# RaspPlaca.net
KiCad netlist of a schematic drawn in EAGLE
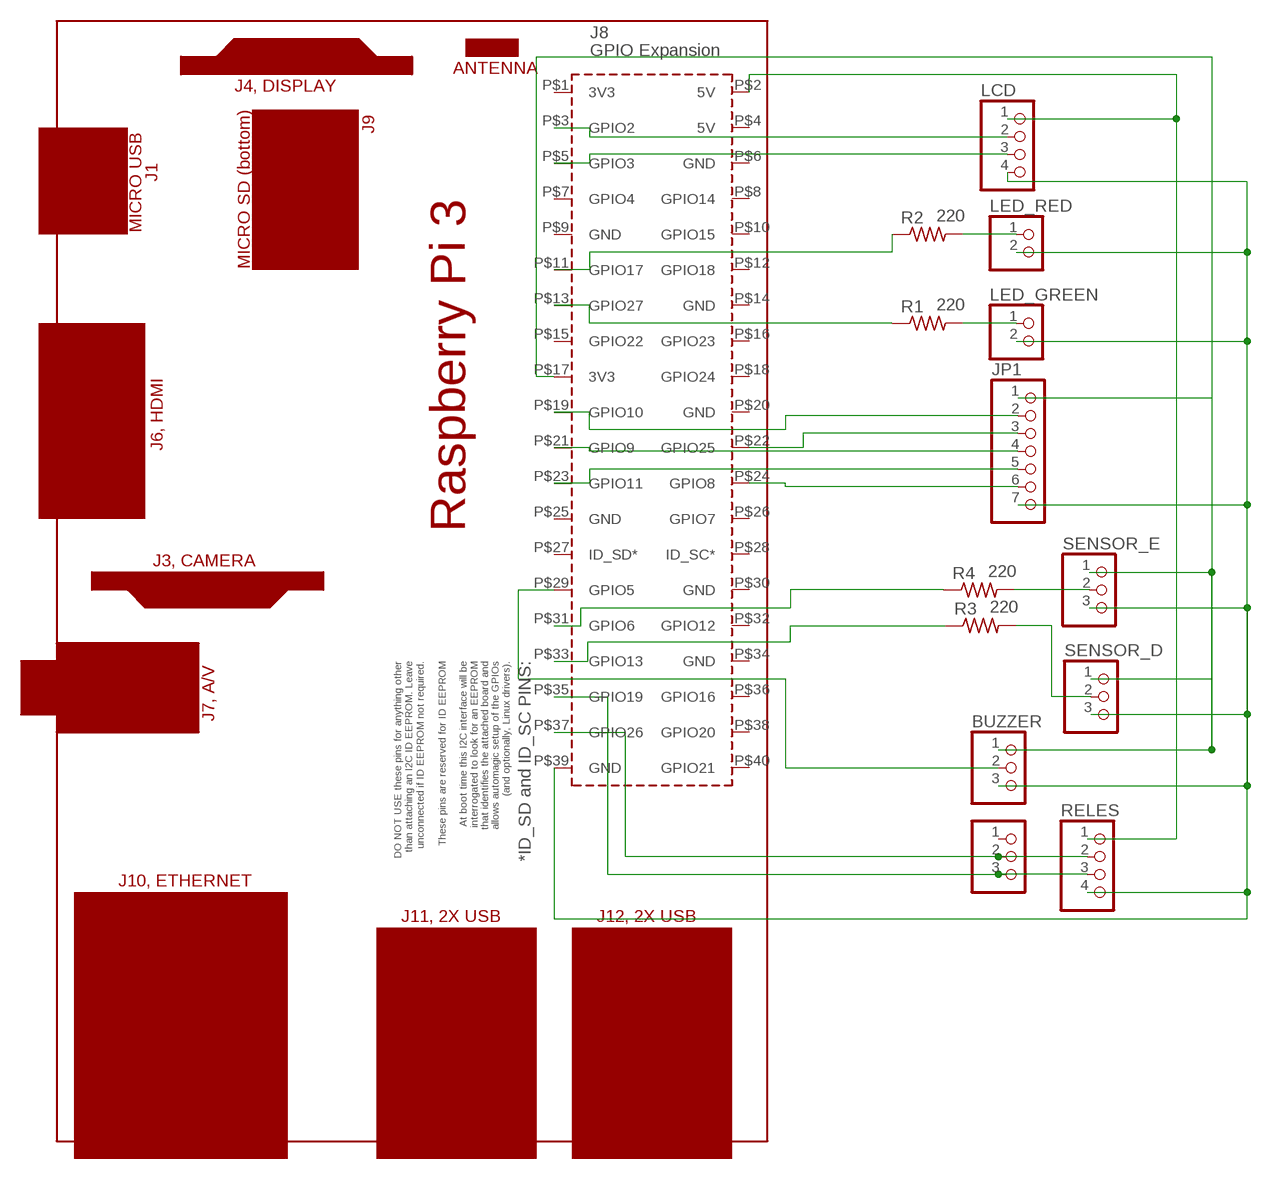
[diagram p0: schematic, sheet 1]

(export (version "E")
  (design (tool "Eeschema 10.0.6"))
  (components
    (comp (ref "BUZZER")
      (value "PINHD-1X3")
      (footprint "eagle-import:1X03")
      (libsource (lib "eagle-import") (part "PINHD-1X3"))
    )
    (comp (ref "JP1")
      (value "PINHD-1X7")
      (footprint "eagle-import:1X07")
      (libsource (lib "eagle-import") (part "PINHD-1X7"))
    )
    (comp (ref "LCD")
      (value "PINHD-1X4")
      (footprint "eagle-import:1X04")
      (libsource (lib "eagle-import") (part "PINHD-1X4"))
    )
    (comp (ref "LED_GREEN")
      (value "PINHD-1X2")
      (footprint "eagle-import:1X02")
      (libsource (lib "eagle-import") (part "PINHD-1X2"))
    )
    (comp (ref "LED_RED")
      (value "PINHD-1X2")
      (footprint "eagle-import:1X02")
      (libsource (lib "eagle-import") (part "PINHD-1X2"))
    )
    (comp (ref "PCB1")
      (value "RPI3RPI3")
      (footprint "eagle-import:RPI3")
      (libsource (lib "eagle-import") (part "RPI3RPI3"))
    )
    (comp (ref "R1")
      (value "220")
      (footprint "eagle-import:0207_10")
      (libsource (lib "eagle-import") (part "R-US_0207/10"))
    )
    (comp (ref "R2")
      (value "220")
      (footprint "eagle-import:0207_10")
      (libsource (lib "eagle-import") (part "R-US_0207/10"))
    )
    (comp (ref "R3")
      (value "220")
      (footprint "eagle-import:0207_10")
      (libsource (lib "eagle-import") (part "R-US_0207/10"))
    )
    (comp (ref "R4")
      (value "220")
      (footprint "eagle-import:0207_10")
      (libsource (lib "eagle-import") (part "R-US_0207/10"))
    )
    (comp (ref "RELES")
      (value "PINHD-1X4")
      (footprint "eagle-import:1X04")
      (libsource (lib "eagle-import") (part "PINHD-1X4"))
    )
    (comp (ref "SENSOR_D")
      (value "PINHD-1X3")
      (footprint "eagle-import:1X03")
      (libsource (lib "eagle-import") (part "PINHD-1X3"))
    )
    (comp (ref "SENSOR_E")
      (value "PINHD-1X3")
      (footprint "eagle-import:1X03")
      (libsource (lib "eagle-import") (part "PINHD-1X3"))
    )
    (comp (ref "UNIFICADOR_RELES")
      (value "PINHD-1X3")
      (footprint "eagle-import:1X03")
      (libsource (lib "eagle-import") (part "PINHD-1X3"))
    )
  )
  (nets
    (net (code "1") (name "Net-(BUZZER-Pad1)") (class "Default")
      (node (ref "BUZZER") (pin "1") (pinfunction "1_1") (pintype "passive"))
      (node (ref "JP1") (pin "1") (pinfunction "1_1") (pintype "passive"))
      (node (ref "PCB1") (pin "P$17") (pinfunction "3V3_P$17") (pintype "bidirectional"))
      (node (ref "SENSOR_D") (pin "1") (pinfunction "1_1") (pintype "passive"))
      (node (ref "SENSOR_E") (pin "1") (pinfunction "1_1") (pintype "passive"))
    )
    (net (code "2") (name "Net-(BUZZER-Pad3)") (class "Default")
      (node (ref "BUZZER") (pin "3") (pinfunction "3_3") (pintype "passive"))
      (node (ref "JP1") (pin "7") (pinfunction "7_7") (pintype "passive"))
      (node (ref "LCD") (pin "4") (pinfunction "4_4") (pintype "passive"))
      (node (ref "LED_GREEN") (pin "2") (pinfunction "2_2") (pintype "passive"))
      (node (ref "LED_RED") (pin "2") (pinfunction "2_2") (pintype "passive"))
      (node (ref "PCB1") (pin "P$39") (pinfunction "GND_P$39") (pintype "bidirectional"))
      (node (ref "RELES") (pin "4") (pinfunction "4_4") (pintype "passive"))
      (node (ref "SENSOR_D") (pin "3") (pinfunction "3_3") (pintype "passive"))
      (node (ref "SENSOR_E") (pin "3") (pinfunction "3_3") (pintype "passive"))
    )
    (net (code "3") (name "Net-(LCD-Pad1)") (class "Default")
      (node (ref "LCD") (pin "1") (pinfunction "1_1") (pintype "passive"))
      (node (ref "PCB1") (pin "P$2") (pinfunction "5V_P$2") (pintype "bidirectional"))
      (node (ref "RELES") (pin "1") (pinfunction "1_1") (pintype "passive"))
    )
    (net (code "4") (name "Net-(LED_GREEN-Pad1)") (class "Default")
      (node (ref "LED_GREEN") (pin "1") (pinfunction "1_1") (pintype "passive"))
      (node (ref "R1") (pin "2") (pinfunction "2_2") (pintype "passive"))
    )
    (net (code "5") (name "Net-(LED_RED-Pad1)") (class "Default")
      (node (ref "LED_RED") (pin "1") (pinfunction "1_1") (pintype "passive"))
      (node (ref "R2") (pin "2") (pinfunction "2_2") (pintype "passive"))
    )
    (net (code "6") (name "Net-(PCB1-GPIO2)") (class "Default")
      (node (ref "LCD") (pin "2") (pinfunction "2_2") (pintype "passive"))
      (node (ref "PCB1") (pin "P$3") (pinfunction "GPIO2_P$3") (pintype "bidirectional"))
    )
    (net (code "7") (name "Net-(PCB1-GPIO3)") (class "Default")
      (node (ref "LCD") (pin "3") (pinfunction "3_3") (pintype "passive"))
      (node (ref "PCB1") (pin "P$5") (pinfunction "GPIO3_P$5") (pintype "bidirectional"))
    )
    (net (code "8") (name "Net-(PCB1-GPIO5)") (class "Default")
      (node (ref "BUZZER") (pin "2") (pinfunction "2_2") (pintype "passive"))
      (node (ref "PCB1") (pin "P$29") (pinfunction "GPIO5_P$29") (pintype "bidirectional"))
    )
    (net (code "9") (name "Net-(PCB1-GPIO6)") (class "Default")
      (node (ref "PCB1") (pin "P$31") (pinfunction "GPIO6_P$31") (pintype "bidirectional"))
      (node (ref "R4") (pin "1") (pinfunction "1_1") (pintype "passive"))
    )
    (net (code "10") (name "Net-(PCB1-GPIO8)") (class "Default")
      (node (ref "JP1") (pin "6") (pinfunction "6_6") (pintype "passive"))
      (node (ref "PCB1") (pin "P$24") (pinfunction "GPIO8_P$24") (pintype "bidirectional"))
    )
    (net (code "11") (name "Net-(PCB1-GPIO9)") (class "Default")
      (node (ref "JP1") (pin "4") (pinfunction "4_4") (pintype "passive"))
      (node (ref "PCB1") (pin "P$21") (pinfunction "GPIO9_P$21") (pintype "bidirectional"))
    )
    (net (code "12") (name "Net-(PCB1-GPIO10)") (class "Default")
      (node (ref "JP1") (pin "2") (pinfunction "2_2") (pintype "passive"))
      (node (ref "PCB1") (pin "P$19") (pinfunction "GPIO10_P$19") (pintype "bidirectional"))
    )
    (net (code "13") (name "Net-(PCB1-GPIO11)") (class "Default")
      (node (ref "JP1") (pin "5") (pinfunction "5_5") (pintype "passive"))
      (node (ref "PCB1") (pin "P$23") (pinfunction "GPIO11_P$23") (pintype "bidirectional"))
    )
    (net (code "14") (name "Net-(PCB1-GPIO13)") (class "Default")
      (node (ref "PCB1") (pin "P$33") (pinfunction "GPIO13_P$33") (pintype "bidirectional"))
      (node (ref "R3") (pin "1") (pinfunction "1_1") (pintype "passive"))
    )
    (net (code "15") (name "Net-(PCB1-GPIO17)") (class "Default")
      (node (ref "PCB1") (pin "P$11") (pinfunction "GPIO17_P$11") (pintype "bidirectional"))
      (node (ref "R2") (pin "1") (pinfunction "1_1") (pintype "passive"))
    )
    (net (code "16") (name "Net-(PCB1-GPIO19)") (class "Default")
      (node (ref "PCB1") (pin "P$35") (pinfunction "GPIO19_P$35") (pintype "bidirectional"))
      (node (ref "RELES") (pin "3") (pinfunction "3_3") (pintype "passive"))
      (node (ref "UNIFICADOR_RELES") (pin "3") (pinfunction "3_3") (pintype "passive"))
    )
    (net (code "17") (name "Net-(PCB1-GPIO25)") (class "Default")
      (node (ref "JP1") (pin "3") (pinfunction "3_3") (pintype "passive"))
      (node (ref "PCB1") (pin "P$22") (pinfunction "GPIO25_P$22") (pintype "bidirectional"))
    )
    (net (code "18") (name "Net-(PCB1-GPIO26)") (class "Default")
      (node (ref "PCB1") (pin "P$37") (pinfunction "GPIO26_P$37") (pintype "bidirectional"))
      (node (ref "RELES") (pin "2") (pinfunction "2_2") (pintype "passive"))
      (node (ref "UNIFICADOR_RELES") (pin "2") (pinfunction "2_2") (pintype "passive"))
    )
    (net (code "19") (name "Net-(PCB1-GPIO27)") (class "Default")
      (node (ref "PCB1") (pin "P$13") (pinfunction "GPIO27_P$13") (pintype "bidirectional"))
      (node (ref "R1") (pin "1") (pinfunction "1_1") (pintype "passive"))
    )
    (net (code "20") (name "Net-(R3-Pad2)") (class "Default")
      (node (ref "R3") (pin "2") (pinfunction "2_2") (pintype "passive"))
      (node (ref "SENSOR_D") (pin "2") (pinfunction "2_2") (pintype "passive"))
    )
    (net (code "21") (name "Net-(R4-Pad2)") (class "Default")
      (node (ref "R4") (pin "2") (pinfunction "2_2") (pintype "passive"))
      (node (ref "SENSOR_E") (pin "2") (pinfunction "2_2") (pintype "passive"))
    )
    (net (code "22") (name "unconnected-(PCB1-3V3-PadP$1)") (class "Default")
      (node (ref "PCB1") (pin "P$1") (pinfunction "3V3_P$1") (pintype "bidirectional"))
    )
    (net (code "23") (name "unconnected-(PCB1-5V-PadP$4)") (class "Default")
      (node (ref "PCB1") (pin "P$4") (pinfunction "5V_P$4") (pintype "bidirectional"))
    )
    (net (code "24") (name "unconnected-(PCB1-GND-PadP$6)") (class "Default")
      (node (ref "PCB1") (pin "P$6") (pinfunction "GND_P$6") (pintype "bidirectional"))
    )
    (net (code "25") (name "unconnected-(PCB1-GND-PadP$9)") (class "Default")
      (node (ref "PCB1") (pin "P$9") (pinfunction "GND_P$9") (pintype "bidirectional"))
    )
    (net (code "26") (name "unconnected-(PCB1-GND-PadP$14)") (class "Default")
      (node (ref "PCB1") (pin "P$14") (pinfunction "GND_P$14") (pintype "bidirectional"))
    )
    (net (code "27") (name "unconnected-(PCB1-GND-PadP$20)") (class "Default")
      (node (ref "PCB1") (pin "P$20") (pinfunction "GND_P$20") (pintype "bidirectional"))
    )
    (net (code "28") (name "unconnected-(PCB1-GND-PadP$25)") (class "Default")
      (node (ref "PCB1") (pin "P$25") (pinfunction "GND_P$25") (pintype "bidirectional"))
    )
    (net (code "29") (name "unconnected-(PCB1-GND-PadP$30)") (class "Default")
      (node (ref "PCB1") (pin "P$30") (pinfunction "GND_P$30") (pintype "bidirectional"))
    )
    (net (code "30") (name "unconnected-(PCB1-GND-PadP$34)") (class "Default")
      (node (ref "PCB1") (pin "P$34") (pinfunction "GND_P$34") (pintype "bidirectional"))
    )
    (net (code "31") (name "unconnected-(PCB1-GPIO4-PadP$7)") (class "Default")
      (node (ref "PCB1") (pin "P$7") (pinfunction "GPIO4_P$7") (pintype "bidirectional"))
    )
    (net (code "32") (name "unconnected-(PCB1-GPIO7-PadP$26)") (class "Default")
      (node (ref "PCB1") (pin "P$26") (pinfunction "GPIO7_P$26") (pintype "bidirectional"))
    )
    (net (code "33") (name "unconnected-(PCB1-GPIO12-PadP$32)") (class "Default")
      (node (ref "PCB1") (pin "P$32") (pinfunction "GPIO12_P$32") (pintype "bidirectional"))
    )
    (net (code "34") (name "unconnected-(PCB1-GPIO14-PadP$8)") (class "Default")
      (node (ref "PCB1") (pin "P$8") (pinfunction "GPIO14_P$8") (pintype "bidirectional"))
    )
    (net (code "35") (name "unconnected-(PCB1-GPIO15-PadP$10)") (class "Default")
      (node (ref "PCB1") (pin "P$10") (pinfunction "GPIO15_P$10") (pintype "bidirectional"))
    )
    (net (code "36") (name "unconnected-(PCB1-GPIO16-PadP$36)") (class "Default")
      (node (ref "PCB1") (pin "P$36") (pinfunction "GPIO16_P$36") (pintype "bidirectional"))
    )
    (net (code "37") (name "unconnected-(PCB1-GPIO18-PadP$12)") (class "Default")
      (node (ref "PCB1") (pin "P$12") (pinfunction "GPIO18_P$12") (pintype "bidirectional"))
    )
    (net (code "38") (name "unconnected-(PCB1-GPIO20-PadP$38)") (class "Default")
      (node (ref "PCB1") (pin "P$38") (pinfunction "GPIO20_P$38") (pintype "bidirectional"))
    )
    (net (code "39") (name "unconnected-(PCB1-GPIO21-PadP$40)") (class "Default")
      (node (ref "PCB1") (pin "P$40") (pinfunction "GPIO21_P$40") (pintype "bidirectional"))
    )
    (net (code "40") (name "unconnected-(PCB1-GPIO22-PadP$15)") (class "Default")
      (node (ref "PCB1") (pin "P$15") (pinfunction "GPIO22_P$15") (pintype "bidirectional"))
    )
    (net (code "41") (name "unconnected-(PCB1-GPIO23-PadP$16)") (class "Default")
      (node (ref "PCB1") (pin "P$16") (pinfunction "GPIO23_P$16") (pintype "bidirectional"))
    )
    (net (code "42") (name "unconnected-(PCB1-GPIO24-PadP$18)") (class "Default")
      (node (ref "PCB1") (pin "P$18") (pinfunction "GPIO24_P$18") (pintype "bidirectional"))
    )
    (net (code "43") (name "unconnected-(PCB1-ID_SC*-PadP$28)") (class "Default")
      (node (ref "PCB1") (pin "P$28") (pinfunction "ID_SC*_P$28") (pintype "bidirectional"))
    )
    (net (code "44") (name "unconnected-(PCB1-ID_SD*-PadP$27)") (class "Default")
      (node (ref "PCB1") (pin "P$27") (pinfunction "ID_SD*_P$27") (pintype "bidirectional"))
    )
    (net (code "45") (name "unconnected-(UNIFICADOR_RELES-Pad1)") (class "Default")
      (node (ref "UNIFICADOR_RELES") (pin "1") (pinfunction "1_1") (pintype "passive"))
    )
  )
)
